# CATS-EUROC-PM.net
KiCad netlist of a schematic drawn in Altium Designer
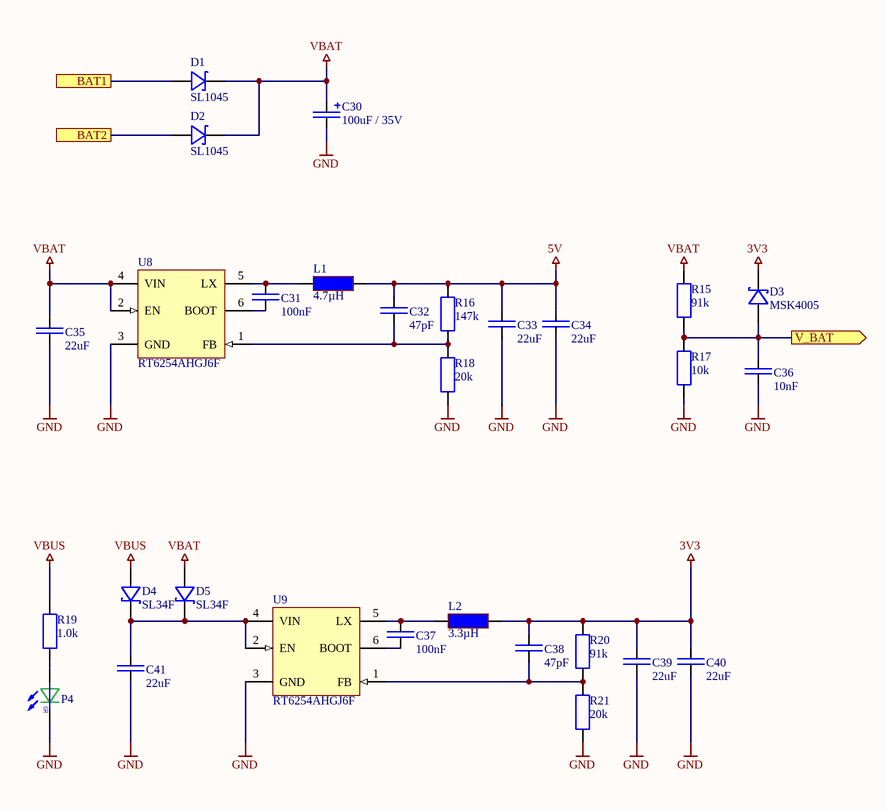
[diagram p0: CATS-EUROC-PM.SchDoc]

(export (version "E")
  (design (tool "Eeschema 10.0.6"))
  (components
    (comp (ref "C30")
      (value "100uF / 35V")
      (footprint "SMD Elko 6.3x7.7")
      (libsource (lib "Electrolytic Capacitors") (part "100uF / 35V"))
    )
    (comp (ref "C31")
      (value "100nF")
      (footprint "SMD Keramikkondensator 0402")
      (description "SMD Ceramic Capacitor E6")
      (libsource (lib "CATS-EUROC") (part "E6 - 100nF"))
    )
    (comp (ref "C32")
      (value "47pF")
      (footprint "SMD Keramikkondensator 0402")
      (description "SMD Ceramic Capacitor E6")
      (libsource (lib "CATS-EUROC") (part "E6 - 47pF"))
    )
    (comp (ref "C33")
      (value "22uF")
      (footprint "SMD Keramikkondensator 0805")
      (description "SMD Ceramic Capacitor E6")
      (libsource (lib "CATS-EUROC") (part "E6 - 22uF"))
    )
    (comp (ref "C34")
      (value "22uF")
      (footprint "SMD Keramikkondensator 0805")
      (description "SMD Ceramic Capacitor E6")
      (libsource (lib "CATS-EUROC") (part "E6 - 22uF"))
    )
    (comp (ref "C35")
      (value "22uF")
      (footprint "SMD Keramikkondensator 0805")
      (description "SMD Ceramic Capacitor E6")
      (libsource (lib "CATS-EUROC") (part "E6 - 22uF"))
    )
    (comp (ref "C36")
      (value "10nF")
      (footprint "SMD Keramikkondensator 0402")
      (description "SMD Ceramic Capacitor E6")
      (libsource (lib "CATS-EUROC") (part "E6 - 10nF"))
    )
    (comp (ref "C37")
      (value "100nF")
      (footprint "SMD Keramikkondensator 0402")
      (description "SMD Ceramic Capacitor E6")
      (libsource (lib "CATS-EUROC") (part "E6 - 100nF"))
    )
    (comp (ref "C38")
      (value "47pF")
      (footprint "SMD Keramikkondensator 0402")
      (description "SMD Ceramic Capacitor E6")
      (libsource (lib "CATS-EUROC") (part "E6 - 47pF"))
    )
    (comp (ref "C39")
      (value "22uF")
      (footprint "SMD Keramikkondensator 0805")
      (description "SMD Ceramic Capacitor E6")
      (libsource (lib "CATS-EUROC") (part "E6 - 22uF"))
    )
    (comp (ref "C40")
      (value "22uF")
      (footprint "SMD Keramikkondensator 0805")
      (description "SMD Ceramic Capacitor E6")
      (libsource (lib "CATS-EUROC") (part "E6 - 22uF"))
    )
    (comp (ref "C41")
      (value "22uF")
      (footprint "SMD Keramikkondensator 0805")
      (description "SMD Ceramic Capacitor E6")
      (libsource (lib "CATS-EUROC") (part "E6 - 22uF"))
    )
    (comp (ref "D1")
      (value "SL1045")
      (footprint "SMD Diode TO-277")
      (description "45V 470mV@10A 10A TO-277 Schottky Barrier Diodes")
      (libsource (lib "Diodes") (part "SL1045"))
    )
    (comp (ref "D2")
      (value "SL1045")
      (footprint "SMD Diode TO-277")
      (description "45V 470mV@10A 10A TO-277 Schottky Barrier Diodes")
      (libsource (lib "Diodes") (part "SL1045"))
    )
    (comp (ref "D3")
      (value "MSK4005")
      (footprint "SMD Diode SOD-523")
      (description "SOD-523 Schottky Barrier Diode")
      (libsource (lib "Diodes") (part "MSK4005"))
    )
    (comp (ref "D4")
      (value "SL34F")
      (footprint "SMD Diode SMAF")
      (description "3A SMAF Schottky Barrier Diode")
      (libsource (lib "Diodes") (part "SL34F"))
    )
    (comp (ref "D5")
      (value "SL34F")
      (footprint "SMD Diode SMAF")
      (description "3A SMAF Schottky Barrier Diode")
      (libsource (lib "Diodes") (part "SL34F"))
    )
    (comp (ref "L1")
      (value "4.7µH")
      (footprint "SMD Inductor 5.5x5.2x3")
      (description "4.7 µH Shielded Molded Inductor 4.5 A 60mOhm Max Nonstandard")
      (libsource (lib "Inductors") (part "Inductor 4.7µH / 4.5A"))
    )
    (comp (ref "L2")
      (value "3.3µH")
      (footprint "SMD Inductor 2x2.5x1.2")
      (description "1.15A 3.3uH ±20% 144mΩ SMD Power Inductors")
      (libsource (lib "Inductors") (part "Inductor 3.3µH / 1.15A"))
    )
    (comp (ref "P4")
      (value "LED")
      (footprint "SMD LED 0603")
      (description "Color LED")
      (libsource (lib "Diodes") (part "LED"))
    )
    (comp (ref "R15")
      (value "91k")
      (footprint "SMD Widerstand 0402")
      (description "SMD Chip Resistor E24")
      (libsource (lib "CATS-EUROC") (part "E24 - 91k"))
    )
    (comp (ref "R16")
      (value "147k")
      (footprint "SMD Widerstand 0402")
      (description "SMD Chip Resistor E96")
      (libsource (lib "CATS-EUROC") (part "E96 - 147k"))
    )
    (comp (ref "R17")
      (value "10k")
      (footprint "SMD Widerstand 0402")
      (description "SMD Chip Resistor E24")
      (libsource (lib "CATS-EUROC") (part "E24 - 10k"))
    )
    (comp (ref "R18")
      (value "20k")
      (footprint "SMD Widerstand 0402")
      (description "SMD Chip Resistor E96")
      (libsource (lib "CATS-EUROC") (part "E96 - 20k"))
    )
    (comp (ref "R19")
      (value "1.0k")
      (footprint "SMD Widerstand 0402")
      (description "SMD Chip Resistor E24")
      (libsource (lib "CATS-EUROC") (part "E24 - 1.0k"))
    )
    (comp (ref "R20")
      (value "91k")
      (footprint "SMD Widerstand 0402")
      (description "SMD Chip Resistor E24")
      (libsource (lib "CATS-EUROC") (part "E24 - 91k"))
    )
    (comp (ref "R21")
      (value "20k")
      (footprint "SMD Widerstand 0402")
      (description "SMD Chip Resistor E96")
      (libsource (lib "CATS-EUROC") (part "E96 - 20k"))
    )
    (comp (ref "U8")
      (value "RT6254AHGJ6F")
      (footprint "SMD IC TSOT-23-6")
      (description "Buck Switching Regulator IC Positive Adjustable 0.6V 1 Output 4A SOT-23-6 Thin, TSOT-23-6")
      (libsource (lib "Voltage-Converter") (part "RT6254AHGJ6F"))
    )
    (comp (ref "U9")
      (value "RT6254AHGJ6F")
      (footprint "SMD IC TSOT-23-6")
      (description "Buck Switching Regulator IC Positive Adjustable 0.6V 1 Output 4A SOT-23-6 Thin, TSOT-23-6")
      (libsource (lib "Voltage-Converter") (part "RT6254AHGJ6F"))
    )
  )
  (nets
    (net (code "1") (name "/BAT1") (class "Default")
      (node (ref "D1") (pin "A") (pinfunction "A_A") (pintype "passive"))
    )
    (net (code "2") (name "/BAT2") (class "Default")
      (node (ref "D2") (pin "A") (pinfunction "A_A") (pintype "passive"))
    )
    (net (code "3") (name "/V_BAT") (class "Default")
      (node (ref "C36") (pin "2") (pinfunction "2_2") (pintype "passive"))
      (node (ref "D3") (pin "A") (pinfunction "A_A") (pintype "passive"))
      (node (ref "R15") (pin "1") (pinfunction "1_1") (pintype "passive"))
      (node (ref "R17") (pin "2") (pinfunction "2_2") (pintype "passive"))
    )
    (net (code "4") (name "3V3") (class "Default")
      (node (ref "C38") (pin "2") (pinfunction "2_2") (pintype "passive"))
      (node (ref "C39") (pin "2") (pinfunction "2_2") (pintype "passive"))
      (node (ref "C40") (pin "2") (pinfunction "2_2") (pintype "passive"))
      (node (ref "D3") (pin "K") (pinfunction "K_K") (pintype "passive"))
      (node (ref "L2") (pin "2") (pinfunction "2_2") (pintype "passive"))
      (node (ref "R20") (pin "2") (pinfunction "2_2") (pintype "passive"))
    )
    (net (code "5") (name "5V") (class "Default")
      (node (ref "C32") (pin "2") (pinfunction "2_2") (pintype "passive"))
      (node (ref "C33") (pin "2") (pinfunction "2_2") (pintype "passive"))
      (node (ref "C34") (pin "2") (pinfunction "2_2") (pintype "passive"))
      (node (ref "L1") (pin "2") (pinfunction "2_2") (pintype "passive"))
      (node (ref "R16") (pin "2") (pinfunction "2_2") (pintype "passive"))
    )
    (net (code "6") (name "GND") (class "Default")
      (node (ref "C30") (pin "M") (pinfunction "-_M") (pintype "passive"))
      (node (ref "C33") (pin "1") (pinfunction "1_1") (pintype "passive"))
      (node (ref "C34") (pin "1") (pinfunction "1_1") (pintype "passive"))
      (node (ref "C35") (pin "1") (pinfunction "1_1") (pintype "passive"))
      (node (ref "C36") (pin "1") (pinfunction "1_1") (pintype "passive"))
      (node (ref "C39") (pin "1") (pinfunction "1_1") (pintype "passive"))
      (node (ref "C40") (pin "1") (pinfunction "1_1") (pintype "passive"))
      (node (ref "C41") (pin "1") (pinfunction "1_1") (pintype "passive"))
      (node (ref "P4") (pin "K") (pinfunction "K_K") (pintype "passive"))
      (node (ref "R17") (pin "1") (pinfunction "1_1") (pintype "passive"))
      (node (ref "R18") (pin "1") (pinfunction "1_1") (pintype "passive"))
      (node (ref "R21") (pin "1") (pinfunction "1_1") (pintype "passive"))
      (node (ref "U8") (pin "3") (pinfunction "GND_3") (pintype "passive"))
      (node (ref "U9") (pin "3") (pinfunction "GND_3") (pintype "passive"))
    )
    (net (code "7") (name "Net-(P4-PadA)") (class "Default")
      (node (ref "P4") (pin "A") (pinfunction "A_A") (pintype "passive"))
      (node (ref "R19") (pin "1") (pinfunction "1_1") (pintype "passive"))
    )
    (net (code "8") (name "Net-(U8-BOOT)") (class "Default")
      (node (ref "C31") (pin "1") (pinfunction "1_1") (pintype "passive"))
      (node (ref "U8") (pin "6") (pinfunction "BOOT_6") (pintype "passive"))
    )
    (net (code "9") (name "Net-(U8-FB)") (class "Default")
      (node (ref "C32") (pin "1") (pinfunction "1_1") (pintype "passive"))
      (node (ref "R16") (pin "1") (pinfunction "1_1") (pintype "passive"))
      (node (ref "R18") (pin "2") (pinfunction "2_2") (pintype "passive"))
      (node (ref "U8") (pin "1") (pinfunction "FB_1") (pintype "input"))
    )
    (net (code "10") (name "Net-(U8-LX)") (class "Default")
      (node (ref "C31") (pin "2") (pinfunction "2_2") (pintype "passive"))
      (node (ref "L1") (pin "1") (pinfunction "1_1") (pintype "passive"))
      (node (ref "U8") (pin "5") (pinfunction "LX_5") (pintype "passive"))
    )
    (net (code "11") (name "Net-(U9-BOOT)") (class "Default")
      (node (ref "C37") (pin "1") (pinfunction "1_1") (pintype "passive"))
      (node (ref "U9") (pin "6") (pinfunction "BOOT_6") (pintype "passive"))
    )
    (net (code "12") (name "Net-(U9-EN)") (class "Default")
      (node (ref "C41") (pin "2") (pinfunction "2_2") (pintype "passive"))
      (node (ref "D4") (pin "K") (pinfunction "K_K") (pintype "passive"))
      (node (ref "D5") (pin "K") (pinfunction "K_K") (pintype "passive"))
      (node (ref "U9") (pin "2") (pinfunction "EN_2") (pintype "input"))
      (node (ref "U9") (pin "4") (pinfunction "VIN_4") (pintype "passive"))
    )
    (net (code "13") (name "Net-(U9-FB)") (class "Default")
      (node (ref "C38") (pin "1") (pinfunction "1_1") (pintype "passive"))
      (node (ref "R20") (pin "1") (pinfunction "1_1") (pintype "passive"))
      (node (ref "R21") (pin "2") (pinfunction "2_2") (pintype "passive"))
      (node (ref "U9") (pin "1") (pinfunction "FB_1") (pintype "input"))
    )
    (net (code "14") (name "Net-(U9-LX)") (class "Default")
      (node (ref "C37") (pin "2") (pinfunction "2_2") (pintype "passive"))
      (node (ref "L2") (pin "1") (pinfunction "1_1") (pintype "passive"))
      (node (ref "U9") (pin "5") (pinfunction "LX_5") (pintype "passive"))
    )
    (net (code "15") (name "VBAT") (class "Default")
      (node (ref "C30") (pin "P") (pinfunction "+_P") (pintype "passive"))
      (node (ref "C35") (pin "2") (pinfunction "2_2") (pintype "passive"))
      (node (ref "D1") (pin "K") (pinfunction "K_K") (pintype "passive"))
      (node (ref "D2") (pin "K") (pinfunction "K_K") (pintype "passive"))
      (node (ref "D5") (pin "A") (pinfunction "A_A") (pintype "passive"))
      (node (ref "R15") (pin "2") (pinfunction "2_2") (pintype "passive"))
      (node (ref "U8") (pin "2") (pinfunction "EN_2") (pintype "input"))
      (node (ref "U8") (pin "4") (pinfunction "VIN_4") (pintype "passive"))
    )
    (net (code "16") (name "VBUS") (class "Default")
      (node (ref "D4") (pin "A") (pinfunction "A_A") (pintype "passive"))
      (node (ref "R19") (pin "2") (pinfunction "2_2") (pintype "passive"))
    )
  )
)
